# LEDS_AND_DRIVER.net
KiCad netlist of a schematic drawn in Altium Designer
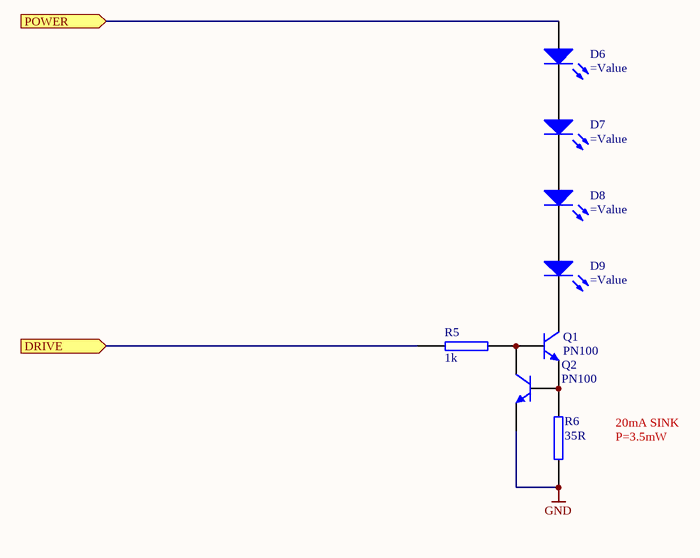
[diagram p0: LEDS AND DRIVER.SchDoc]

(export (version "E")
  (design (tool "Eeschema 10.0.6"))
  (components
    (comp (ref "D6")
      (value "~")
      (footprint "LED(3D) 5MM VERTICAL (YELLOW)")
      (description "LED 55")
      (libsource (lib "NASCO") (part "LED 3mm RED"))
    )
    (comp (ref "D7")
      (value "~")
      (footprint "LED(3D) 5MM VERTICAL (YELLOW)")
      (description "LED 55")
      (libsource (lib "NASCO") (part "LED 3mm RED"))
    )
    (comp (ref "D8")
      (value "~")
      (footprint "LED(3D) 5MM VERTICAL (YELLOW)")
      (description "LED 55")
      (libsource (lib "NASCO") (part "LED 3mm RED"))
    )
    (comp (ref "D9")
      (value "~")
      (footprint "LED(3D) 5MM VERTICAL (YELLOW)")
      (description "LED 55")
      (libsource (lib "NASCO") (part "LED 3mm RED"))
    )
    (comp (ref "Q1")
      (value "PN100")
      (footprint "TO-92")
      (description "NPN Bipolar Transistor")
      (libsource (lib "tail lights") (part "PN100"))
    )
    (comp (ref "Q2")
      (value "PN100")
      (footprint "TO-92")
      (description "NPN Bipolar Transistor")
      (libsource (lib "tail lights") (part "PN100"))
    )
    (comp (ref "R5")
      (value "1k")
      (footprint "AXIAL-0.4")
      (description "RESISTOR SMD 0603 1k")
      (libsource (lib "NASCO Resistors") (part "RES SMD 0603 1k"))
    )
    (comp (ref "R6")
      (value "35R")
      (footprint "AXIAL-0.4")
      (description "RESISTOR SMD 0603 1k")
      (libsource (lib "NASCO Resistors") (part "RES SMD 0603 1k"))
    )
  )
  (nets
    (net (code "1") (name "/DRIVE") (class "Default")
      (node (ref "R5") (pin "2") (pinfunction "2_2") (pintype "passive"))
    )
    (net (code "2") (name "/POWER") (class "Default")
      (node (ref "D6") (pin "1") (pinfunction "A_1") (pintype "passive"))
    )
    (net (code "3") (name "GND") (class "Default")
      (node (ref "Q2") (pin "1") (pinfunction "E_1") (pintype "passive"))
      (node (ref "R6") (pin "1") (pinfunction "1_1") (pintype "passive"))
    )
    (net (code "4") (name "Net-(D6-K)") (class "Default")
      (node (ref "D6") (pin "2") (pinfunction "K_2") (pintype "passive"))
      (node (ref "D7") (pin "1") (pinfunction "A_1") (pintype "passive"))
    )
    (net (code "5") (name "Net-(D7-K)") (class "Default")
      (node (ref "D7") (pin "2") (pinfunction "K_2") (pintype "passive"))
      (node (ref "D8") (pin "1") (pinfunction "A_1") (pintype "passive"))
    )
    (net (code "6") (name "Net-(D8-K)") (class "Default")
      (node (ref "D8") (pin "2") (pinfunction "K_2") (pintype "passive"))
      (node (ref "D9") (pin "1") (pinfunction "A_1") (pintype "passive"))
    )
    (net (code "7") (name "Net-(D9-K)") (class "Default")
      (node (ref "D9") (pin "2") (pinfunction "K_2") (pintype "passive"))
      (node (ref "Q1") (pin "3") (pinfunction "C_3") (pintype "passive"))
    )
    (net (code "8") (name "Net-(Q1-B)") (class "Default")
      (node (ref "Q1") (pin "2") (pinfunction "B_2") (pintype "passive"))
      (node (ref "Q2") (pin "3") (pinfunction "C_3") (pintype "passive"))
      (node (ref "R5") (pin "1") (pinfunction "1_1") (pintype "passive"))
    )
    (net (code "9") (name "Net-(Q1-E)") (class "Default")
      (node (ref "Q1") (pin "1") (pinfunction "E_1") (pintype "passive"))
      (node (ref "Q2") (pin "2") (pinfunction "B_2") (pintype "passive"))
      (node (ref "R6") (pin "2") (pinfunction "2_2") (pintype "passive"))
    )
  )
)
